# Sheet_1-copy_2025-07-01.net
KiCad netlist of a schematic drawn in Altium Designer
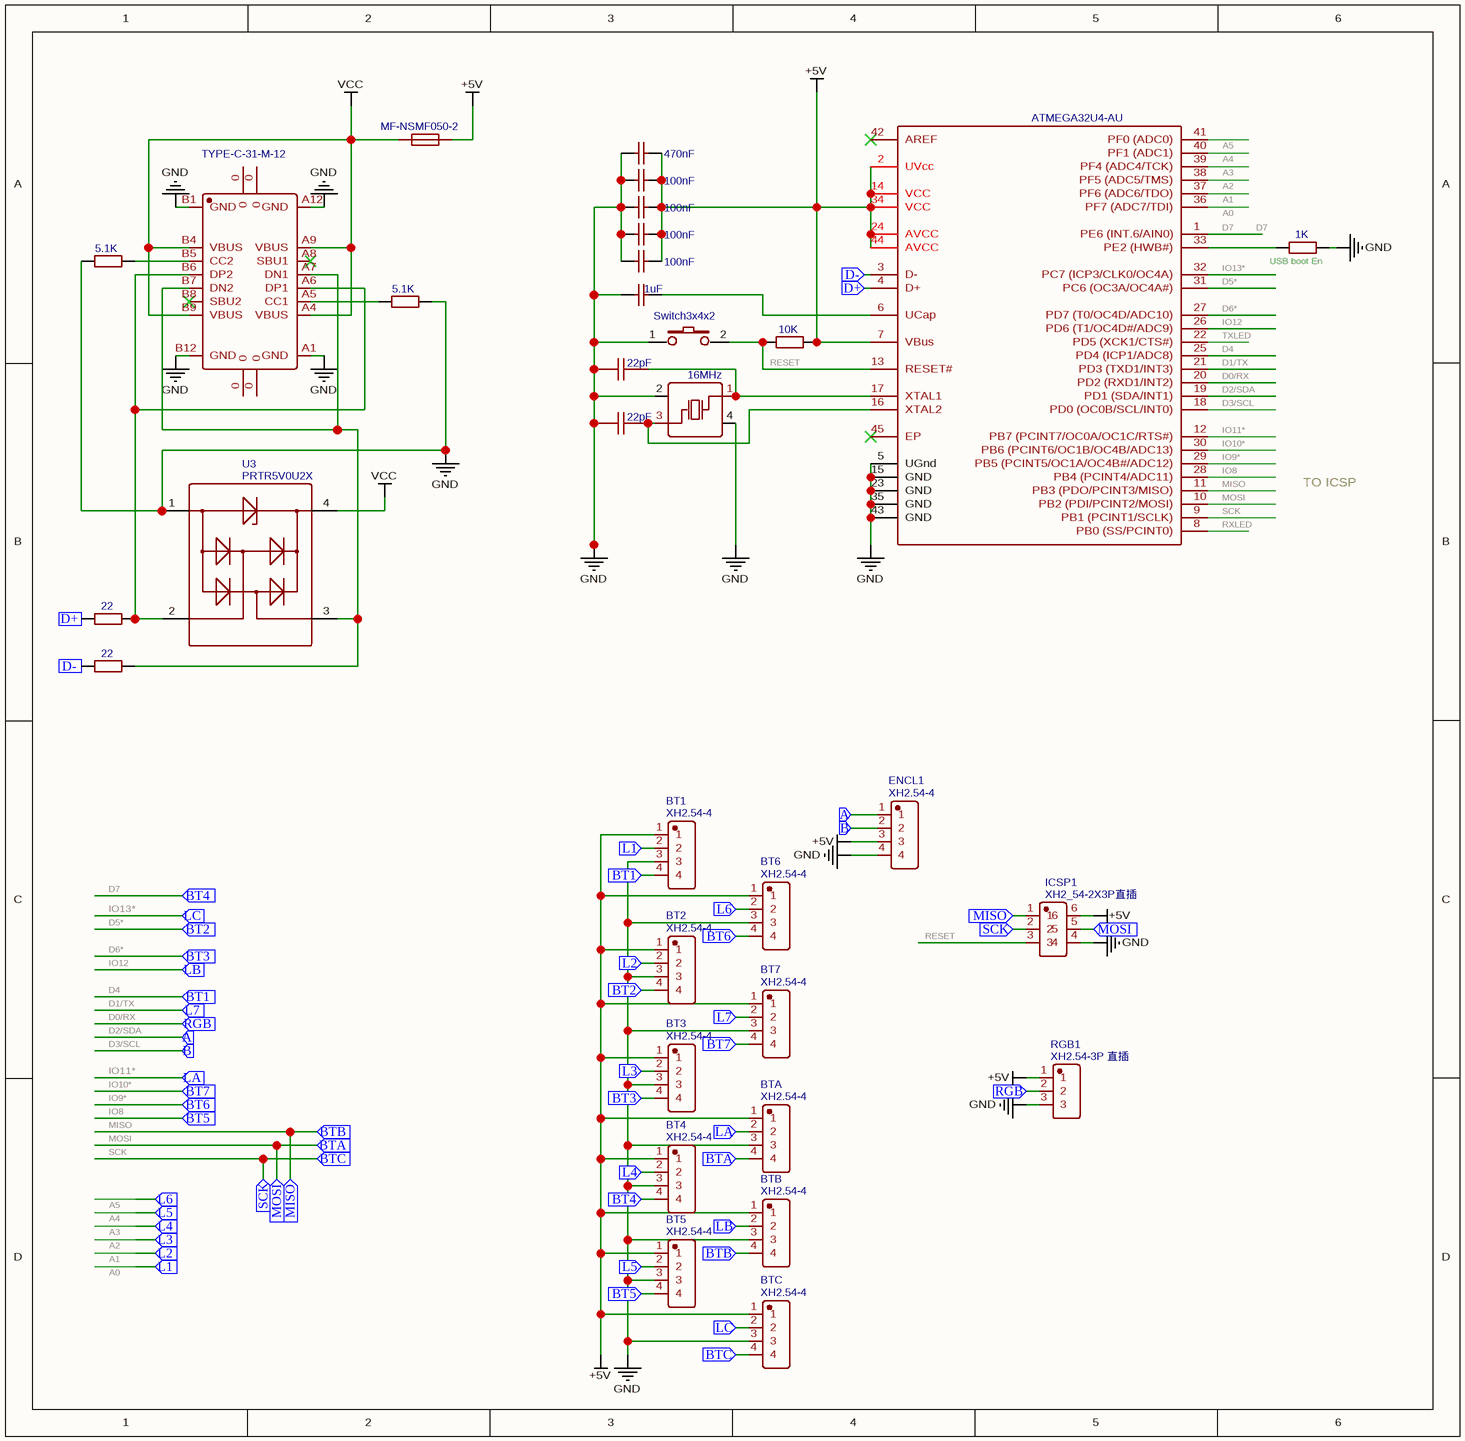
[diagram p0: Sheet_1-copy_2025-07-01.schdoc]

(export (version "E")
  (design (tool "Eeschema 10.0.6"))
  (components
    (comp (ref "BT1")
      (value "XH2.54-4")
      (fields (field (name "CONTRIBUTOR") "LCSC"))
      (libsource (lib "altium-import") (part "root_0_XH2.54-4_"))
    )
    (comp (ref "BT2")
      (value "XH2.54-4")
      (fields (field (name "CONTRIBUTOR") "LCSC"))
      (libsource (lib "altium-import") (part "root_0_XH2.54-4_"))
    )
    (comp (ref "BT3")
      (value "XH2.54-4")
      (fields (field (name "CONTRIBUTOR") "LCSC"))
      (libsource (lib "altium-import") (part "root_0_XH2.54-4_"))
    )
    (comp (ref "BT4")
      (value "XH2.54-4")
      (fields (field (name "CONTRIBUTOR") "LCSC"))
      (libsource (lib "altium-import") (part "root_0_XH2.54-4_"))
    )
    (comp (ref "BT5")
      (value "XH2.54-4")
      (fields (field (name "CONTRIBUTOR") "LCSC"))
      (libsource (lib "altium-import") (part "root_0_XH2.54-4_"))
    )
    (comp (ref "BT6")
      (value "XH2.54-4")
      (fields (field (name "CONTRIBUTOR") "LCSC"))
      (libsource (lib "altium-import") (part "root_0_XH2.54-4_"))
    )
    (comp (ref "BT7")
      (value "XH2.54-4")
      (fields (field (name "CONTRIBUTOR") "LCSC"))
      (libsource (lib "altium-import") (part "root_0_XH2.54-4_"))
    )
    (comp (ref "BTA")
      (value "XH2.54-4")
      (fields (field (name "CONTRIBUTOR") "LCSC"))
      (libsource (lib "altium-import") (part "root_0_XH2.54-4_"))
    )
    (comp (ref "BTB")
      (value "XH2.54-4")
      (fields (field (name "CONTRIBUTOR") "LCSC"))
      (libsource (lib "altium-import") (part "root_0_XH2.54-4_"))
    )
    (comp (ref "BTC")
      (value "XH2.54-4")
      (fields (field (name "CONTRIBUTOR") "LCSC"))
      (libsource (lib "altium-import") (part "root_0_XH2.54-4_"))
    )
    (comp (ref "C9")
      (value "22pF")
      (fields
        (field (name "MANUFACTURER") "SAMSUNG")
        (field (name "MANUFACTURER PART") "CL10C220JB81PNC")
        (field (name "CONTRIBUTOR") "LCSC")
      )
      (libsource (lib "altium-import") (part "root_2_22pF_"))
    )
    (comp (ref "C10")
      (value "22pF")
      (fields
        (field (name "MANUFACTURER") "SAMSUNG")
        (field (name "MANUFACTURER PART") "CL10C220JB81PNC")
        (field (name "CONTRIBUTOR") "LCSC")
      )
      (libsource (lib "altium-import") (part "root_2_22pF_"))
    )
    (comp (ref "C11")
      (value "100nF")
      (fields (field (name "MANUFACTURER PART") "CL10B104JB8NNNC") (field (name "MANUFACTURER") "SAMSUNG"))
      (libsource (lib "altium-import") (part "root_0_100nF_"))
    )
    (comp (ref "C12")
      (value "100nF")
      (fields (field (name "MANUFACTURER PART") "CL10B104JB8NNNC") (field (name "MANUFACTURER") "SAMSUNG"))
      (libsource (lib "altium-import") (part "root_0_100nF_"))
    )
    (comp (ref "C13")
      (value "100nF")
      (fields (field (name "MANUFACTURER PART") "CL10B104JB8NNNC") (field (name "MANUFACTURER") "SAMSUNG"))
      (libsource (lib "altium-import") (part "root_0_100nF_"))
    )
    (comp (ref "C14")
      (value "100nF")
      (fields (field (name "MANUFACTURER PART") "CL10B104JB8NNNC") (field (name "MANUFACTURER") "SAMSUNG"))
      (libsource (lib "altium-import") (part "root_0_100nF_"))
    )
    (comp (ref "C15")
      (value "470nF")
      (fields (field (name "MANUFACTURER PART") "CL10B474KA8NNNC") (field (name "MANUFACTURER") "SAMSUNG"))
      (libsource (lib "altium-import") (part "root_0_470nF_"))
    )
    (comp (ref "C16")
      (value "1uF")
      (fields (field (name "MANUFACTURER PART") "CL10A105KB8NNNC") (field (name "MANUFACTURER") "SAMSUNG"))
      (libsource (lib "altium-import") (part "root_0_1uF_"))
    )
    (comp (ref "ENCL1")
      (value "XH2.54-4")
      (fields (field (name "CONTRIBUTOR") "LCSC"))
      (libsource (lib "altium-import") (part "root_0_XH2.54-4_"))
    )
    (comp (ref "ICSP1")
      (value "XH2_54-2X3P直插")
      (fields (field (name "CONTRIBUTOR") "LCSC"))
      (libsource (lib "altium-import") (part "root_0_XH2_54-2X3P直插_"))
    )
    (comp (ref "KEY2")
      (value "Switch3x4x2")
      (fields (field (name "MANUFACTURER") "ReliaPro"))
      (libsource (lib "altium-import") (part "root_0_Switch3x4x2_"))
    )
    (comp (ref "R1")
      (value "10K")
      (fields (field (name "MANUFACTURER") "UniOhm") (field (name "MANUFACTURER PART") "0805W8F1002T5E"))
      (libsource (lib "altium-import") (part "root_0_10K_"))
    )
    (comp (ref "R2")
      (value "1K")
      (fields (field (name "MANUFACTURER") "UniOhm") (field (name "MANUFACTURER PART") "TC0525F1001T5E"))
      (libsource (lib "altium-import") (part "root_0_1K_"))
    )
    (comp (ref "R3")
      (value "5.1K")
      (fields (field (name "MANUFACTURER") "UniOhm") (field (name "MANUFACTURER PART") "0805W8F5101T5E"))
      (libsource (lib "altium-import") (part "root_0_5.1K_"))
    )
    (comp (ref "R4")
      (value "5.1K")
      (fields (field (name "MANUFACTURER") "UniOhm") (field (name "MANUFACTURER PART") "0805W8F5101T5E"))
      (libsource (lib "altium-import") (part "root_0_5.1K_"))
    )
    (comp (ref "R5")
      (value "22")
      (fields (field (name "MANUFACTURER") "UniOhm") (field (name "MANUFACTURER PART") "0603WAF220JT5E"))
      (libsource (lib "altium-import") (part "root_0_22_"))
    )
    (comp (ref "R6")
      (value "22")
      (fields (field (name "MANUFACTURER") "UniOhm") (field (name "MANUFACTURER PART") "0603WAF220JT5E"))
      (libsource (lib "altium-import") (part "root_0_22_"))
    )
    (comp (ref "RGB1")
      (value "XH2.54-3P 直插")
      (fields (field (name "CONTRIBUTOR") "LCSC"))
      (libsource (lib "altium-import") (part "root_0_XH2.54-3P 直插_"))
    )
    (comp (ref "U2")
      (value "MF-NSMF050-2")
      (fields (field (name "MANUFACTURER") "BOURNS"))
      (libsource (lib "altium-import") (part "root_0_MF-NSMF050-2_"))
    )
    (comp (ref "U3")
      (value "PRTR5V0U2X")
      (fields (field (name "MANUFACTURER") "Yenji Elec") (field (name "CONTRIBUTOR") "LCSC"))
      (libsource (lib "altium-import") (part "root_0_PRTR5V0U2X_"))
    )
    (comp (ref "U77")
      (value "ATMEGA32U4-AU")
      (fields (field (name "MANUFACTURER") "MICROCHIP") (field (name "MANUFACTURER PART") "ATMEGA32U4-MU"))
      (libsource (lib "altium-import") (part "root_0_ATMEGA32U4-AU_"))
    )
    (comp (ref "USBC2")
      (value "TYPE-C-31-M-12")
      (fields
        (field (name "MANUFACTURER") "Rectangular Connectors - Contacts")
        (field (name "CONTRIBUTOR") "LCSC")
      )
      (libsource (lib "altium-import") (part "root_0_TYPE-C-31-M-12_"))
    )
    (comp (ref "X1")
      (value "16MHz")
      (fields (field (name "MANUFACTURER") "YXC") (field (name "MANUFACTURER PART") "X322516MRB4SI"))
      (libsource (lib "altium-import") (part "root_2_16MHz_"))
    )
  )
  (nets
    (net (code "1") (name "+5V") (class "Default")
      (node (ref "BT1") (pin "1") (pinfunction "1_1") (pintype "passive"))
      (node (ref "BT2") (pin "1") (pinfunction "1_1") (pintype "passive"))
      (node (ref "BT3") (pin "1") (pinfunction "1_1") (pintype "passive"))
      (node (ref "BT4") (pin "1") (pinfunction "1_1") (pintype "passive"))
      (node (ref "BT5") (pin "1") (pinfunction "1_1") (pintype "passive"))
      (node (ref "BT6") (pin "1") (pinfunction "1_1") (pintype "passive"))
      (node (ref "BT7") (pin "1") (pinfunction "1_1") (pintype "passive"))
      (node (ref "BTA") (pin "1") (pinfunction "1_1") (pintype "passive"))
      (node (ref "BTB") (pin "1") (pinfunction "1_1") (pintype "passive"))
      (node (ref "BTC") (pin "1") (pinfunction "1_1") (pintype "passive"))
      (node (ref "C11") (pin "2") (pinfunction "2_2") (pintype "passive"))
      (node (ref "C12") (pin "2") (pinfunction "2_2") (pintype "passive"))
      (node (ref "C13") (pin "2") (pinfunction "2_2") (pintype "passive"))
      (node (ref "C14") (pin "2") (pinfunction "2_2") (pintype "passive"))
      (node (ref "C15") (pin "2") (pinfunction "2_2") (pintype "passive"))
      (node (ref "ENCL1") (pin "3") (pinfunction "3_3") (pintype "passive"))
      (node (ref "ICSP1") (pin "6") (pinfunction "6_6") (pintype "passive"))
      (node (ref "R1") (pin "2") (pinfunction "2_2") (pintype "passive"))
      (node (ref "RGB1") (pin "1") (pinfunction "1_1") (pintype "passive"))
      (node (ref "U2") (pin "2") (pinfunction "2_2") (pintype "passive"))
      (node (ref "U77") (pin "14") (pinfunction "VCC_14") (pintype "passive"))
      (node (ref "U77") (pin "2") (pinfunction "UVcc_2") (pintype "passive"))
      (node (ref "U77") (pin "24") (pinfunction "AVCC_24") (pintype "passive"))
      (node (ref "U77") (pin "34") (pinfunction "VCC_34") (pintype "passive"))
      (node (ref "U77") (pin "44") (pinfunction "AVCC_44") (pintype "passive"))
      (node (ref "U77") (pin "7") (pinfunction "VBus_7") (pintype "passive"))
    )
    (net (code "2") (name "/A0") (class "Default")
      (node (ref "BT1") (pin "2") (pinfunction "2_2") (pintype "passive"))
      (node (ref "U77") (pin "36") (pinfunction "PF7_(ADC7/TDI)_36") (pintype "passive"))
    )
    (net (code "3") (name "/A1") (class "Default")
      (node (ref "BT2") (pin "2") (pinfunction "2_2") (pintype "passive"))
      (node (ref "U77") (pin "37") (pinfunction "PF6_(ADC6/TDO)_37") (pintype "passive"))
    )
    (net (code "4") (name "/A2") (class "Default")
      (node (ref "BT3") (pin "2") (pinfunction "2_2") (pintype "passive"))
      (node (ref "U77") (pin "38") (pinfunction "PF5_(ADC5/TMS)_38") (pintype "passive"))
    )
    (net (code "5") (name "/A3") (class "Default")
      (node (ref "BT4") (pin "2") (pinfunction "2_2") (pintype "passive"))
      (node (ref "U77") (pin "39") (pinfunction "PF4_(ADC4/TCK)_39") (pintype "passive"))
    )
    (net (code "6") (name "/A4") (class "Default")
      (node (ref "BT5") (pin "2") (pinfunction "2_2") (pintype "passive"))
      (node (ref "U77") (pin "40") (pinfunction "PF1_(ADC1)_40") (pintype "passive"))
    )
    (net (code "7") (name "/A5") (class "Default")
      (node (ref "BT6") (pin "2") (pinfunction "2_2") (pintype "passive"))
      (node (ref "U77") (pin "41") (pinfunction "PF0_(ADC0)_41") (pintype "passive"))
    )
    (net (code "8") (name "/D+") (class "Default")
      (node (ref "R5") (pin "1") (pinfunction "1_1") (pintype "passive"))
      (node (ref "U77") (pin "4") (pinfunction "D+_4") (pintype "passive"))
    )
    (net (code "9") (name "/D-") (class "Default")
      (node (ref "R6") (pin "1") (pinfunction "1_1") (pintype "passive"))
      (node (ref "U77") (pin "3") (pinfunction "D-_3") (pintype "passive"))
    )
    (net (code "10") (name "/D0{slash}RX") (class "Default")
      (node (ref "RGB1") (pin "2") (pinfunction "2_2") (pintype "passive"))
      (node (ref "U77") (pin "20") (pinfunction "PD2_(RXD1/INT2)_20") (pintype "passive"))
    )
    (net (code "11") (name "/D1{slash}TX") (class "Default")
      (node (ref "BT7") (pin "2") (pinfunction "2_2") (pintype "passive"))
      (node (ref "U77") (pin "21") (pinfunction "PD3_(TXD1/INT3)_21") (pintype "passive"))
    )
    (net (code "12") (name "/D2{slash}SDA") (class "Default")
      (node (ref "ENCL1") (pin "1") (pinfunction "1_1") (pintype "passive"))
      (node (ref "U77") (pin "19") (pinfunction "PD1_(SDA/INT1)_19") (pintype "passive"))
    )
    (net (code "13") (name "/D3{slash}SCL") (class "Default")
      (node (ref "ENCL1") (pin "2") (pinfunction "2_2") (pintype "passive"))
      (node (ref "U77") (pin "18") (pinfunction "PD0_(OC0B/SCL/INT0)_18") (pintype "passive"))
    )
    (net (code "14") (name "/D4") (class "Default")
      (node (ref "BT1") (pin "4") (pinfunction "4_4") (pintype "passive"))
      (node (ref "U77") (pin "25") (pinfunction "PD4_(ICP1/ADC8)_25") (pintype "passive"))
    )
    (net (code "15") (name "/D5*") (class "Default")
      (node (ref "BT2") (pin "4") (pinfunction "4_4") (pintype "passive"))
      (node (ref "U77") (pin "31") (pinfunction "PC6_(OC3A/OC4A#)_31") (pintype "passive"))
    )
    (net (code "16") (name "/D6*") (class "Default")
      (node (ref "BT3") (pin "4") (pinfunction "4_4") (pintype "passive"))
      (node (ref "U77") (pin "27") (pinfunction "PD7_(T0/OC4D/ADC10)_27") (pintype "passive"))
    )
    (net (code "17") (name "/D7") (class "Default")
      (node (ref "BT4") (pin "4") (pinfunction "4_4") (pintype "passive"))
      (node (ref "U77") (pin "1") (pinfunction "PE6_(INT.6/AIN0)_1") (pintype "passive"))
    )
    (net (code "18") (name "/IO8") (class "Default")
      (node (ref "BT5") (pin "4") (pinfunction "4_4") (pintype "passive"))
      (node (ref "U77") (pin "28") (pinfunction "PB4_(PCINT4/ADC11)_28") (pintype "passive"))
    )
    (net (code "19") (name "/IO9*") (class "Default")
      (node (ref "BT6") (pin "4") (pinfunction "4_4") (pintype "passive"))
      (node (ref "U77") (pin "29") (pinfunction "PB5_(PCINT5/OC1A/OC4B#/ADC12)_29") (pintype "passive"))
    )
    (net (code "20") (name "/IO10*") (class "Default")
      (node (ref "BT7") (pin "4") (pinfunction "4_4") (pintype "passive"))
      (node (ref "U77") (pin "30") (pinfunction "PB6_(PCINT6/OC1B/OC4B/ADC13)_30") (pintype "passive"))
    )
    (net (code "21") (name "/IO11*") (class "Default")
      (node (ref "BTA") (pin "2") (pinfunction "2_2") (pintype "passive"))
      (node (ref "U77") (pin "12") (pinfunction "PB7_(PCINT7/OC0A/OC1C/RTS#)_12") (pintype "passive"))
    )
    (net (code "22") (name "/IO12") (class "Default")
      (node (ref "BTB") (pin "2") (pinfunction "2_2") (pintype "passive"))
      (node (ref "U77") (pin "26") (pinfunction "PD6_(T1/OC4D#/ADC9)_26") (pintype "passive"))
    )
    (net (code "23") (name "/IO13*") (class "Default")
      (node (ref "BTC") (pin "2") (pinfunction "2_2") (pintype "passive"))
      (node (ref "U77") (pin "32") (pinfunction "PC7_(ICP3/CLK0/OC4A)_32") (pintype "passive"))
    )
    (net (code "24") (name "/MISO") (class "Default")
      (node (ref "BTB") (pin "4") (pinfunction "4_4") (pintype "passive"))
      (node (ref "ICSP1") (pin "1") (pinfunction "1_1") (pintype "passive"))
      (node (ref "U77") (pin "11") (pinfunction "PB3_(PDO/PCINT3/MISO)_11") (pintype "passive"))
    )
    (net (code "25") (name "/MOSI") (class "Default")
      (node (ref "BTA") (pin "4") (pinfunction "4_4") (pintype "passive"))
      (node (ref "ICSP1") (pin "5") (pinfunction "5_5") (pintype "passive"))
      (node (ref "U77") (pin "10") (pinfunction "PB2_(PDI/PCINT2/MOSI)_10") (pintype "passive"))
    )
    (net (code "26") (name "/RESET") (class "Default")
      (node (ref "ICSP1") (pin "3") (pinfunction "3_3") (pintype "passive"))
      (node (ref "KEY2") (pin "2") (pinfunction "2_2") (pintype "passive"))
      (node (ref "R1") (pin "1") (pinfunction "1_1") (pintype "passive"))
      (node (ref "U77") (pin "13") (pinfunction "RESET#_13") (pintype "passive"))
    )
    (net (code "27") (name "/RXLED") (class "Default")
      (node (ref "U77") (pin "8") (pinfunction "PB0_(SS/PCINT0)_8") (pintype "passive"))
    )
    (net (code "28") (name "/SCK") (class "Default")
      (node (ref "BTC") (pin "4") (pinfunction "4_4") (pintype "passive"))
      (node (ref "ICSP1") (pin "2") (pinfunction "2_2") (pintype "passive"))
      (node (ref "U77") (pin "9") (pinfunction "PB1_(PCINT1/SCLK)_9") (pintype "passive"))
    )
    (net (code "29") (name "/TXLED") (class "Default")
      (node (ref "U77") (pin "22") (pinfunction "PD5_(XCK1/CTS#)_22") (pintype "passive"))
    )
    (net (code "30") (name "GND") (class "Default")
      (node (ref "BT1") (pin "3") (pinfunction "3_3") (pintype "passive"))
      (node (ref "BT2") (pin "3") (pinfunction "3_3") (pintype "passive"))
      (node (ref "BT3") (pin "3") (pinfunction "3_3") (pintype "passive"))
      (node (ref "BT4") (pin "3") (pinfunction "3_3") (pintype "passive"))
      (node (ref "BT5") (pin "3") (pinfunction "3_3") (pintype "passive"))
      (node (ref "BT6") (pin "3") (pinfunction "3_3") (pintype "passive"))
      (node (ref "BT7") (pin "3") (pinfunction "3_3") (pintype "passive"))
      (node (ref "BTA") (pin "3") (pinfunction "3_3") (pintype "passive"))
      (node (ref "BTB") (pin "3") (pinfunction "3_3") (pintype "passive"))
      (node (ref "BTC") (pin "3") (pinfunction "3_3") (pintype "passive"))
      (node (ref "C10") (pin "1") (pinfunction "1_1") (pintype "passive"))
      (node (ref "C11") (pin "1") (pinfunction "1_1") (pintype "passive"))
      (node (ref "C12") (pin "1") (pinfunction "1_1") (pintype "passive"))
      (node (ref "C13") (pin "1") (pinfunction "1_1") (pintype "passive"))
      (node (ref "C14") (pin "1") (pinfunction "1_1") (pintype "passive"))
      (node (ref "C15") (pin "1") (pinfunction "1_1") (pintype "passive"))
      (node (ref "C16") (pin "1") (pinfunction "1_1") (pintype "passive"))
      (node (ref "C9") (pin "1") (pinfunction "1_1") (pintype "passive"))
      (node (ref "ENCL1") (pin "4") (pinfunction "4_4") (pintype "passive"))
      (node (ref "ICSP1") (pin "4") (pinfunction "4_4") (pintype "passive"))
      (node (ref "KEY2") (pin "1") (pinfunction "1_1") (pintype "passive"))
      (node (ref "R2") (pin "2") (pinfunction "2_2") (pintype "passive"))
      (node (ref "R3") (pin "2") (pinfunction "2_2") (pintype "passive"))
      (node (ref "R4") (pin "1") (pinfunction "1_1") (pintype "passive"))
      (node (ref "RGB1") (pin "3") (pinfunction "3_3") (pintype "passive"))
      (node (ref "U3") (pin "1") (pinfunction "GND_1") (pintype "passive"))
      (node (ref "U77") (pin "15") (pinfunction "GND_15") (pintype "passive"))
      (node (ref "U77") (pin "23") (pinfunction "GND_23") (pintype "passive"))
      (node (ref "U77") (pin "35") (pinfunction "GND_35") (pintype "passive"))
      (node (ref "U77") (pin "43") (pinfunction "GND_43") (pintype "passive"))
      (node (ref "U77") (pin "5") (pinfunction "UGnd_5") (pintype "passive"))
      (node (ref "USBC2") (pin "A1") (pinfunction "GND_A1") (pintype "passive"))
      (node (ref "USBC2") (pin "A12") (pinfunction "GND_A12") (pintype "passive"))
      (node (ref "USBC2") (pin "B1") (pinfunction "GND_B1") (pintype "passive"))
      (node (ref "USBC2") (pin "B12") (pinfunction "GND_B12") (pintype "passive"))
      (node (ref "X1") (pin "2") (pinfunction "GND_2") (pintype "passive"))
      (node (ref "X1") (pin "4") (pinfunction "GND_4") (pintype "passive"))
    )
    (net (code "31") (name "Net-(U3-IO1)") (class "Default")
      (node (ref "R5") (pin "2") (pinfunction "2_2") (pintype "passive"))
      (node (ref "U3") (pin "2") (pinfunction "IO1_2") (pintype "passive"))
      (node (ref "USBC2") (pin "A6") (pinfunction "DP1_A6") (pintype "passive"))
      (node (ref "USBC2") (pin "B6") (pinfunction "DP2_B6") (pintype "passive"))
    )
    (net (code "32") (name "Net-(U3-IO2)") (class "Default")
      (node (ref "R6") (pin "2") (pinfunction "2_2") (pintype "passive"))
      (node (ref "U3") (pin "3") (pinfunction "IO2_3") (pintype "passive"))
      (node (ref "USBC2") (pin "A7") (pinfunction "DN1_A7") (pintype "passive"))
      (node (ref "USBC2") (pin "B7") (pinfunction "DN2_B7") (pintype "passive"))
    )
    (net (code "33") (name "Net-(U77-PE2_(HWB#))") (class "Default")
      (node (ref "R2") (pin "1") (pinfunction "1_1") (pintype "passive"))
      (node (ref "U77") (pin "33") (pinfunction "PE2_(HWB#)_33") (pintype "passive"))
    )
    (net (code "34") (name "Net-(U77-UCap)") (class "Default")
      (node (ref "C16") (pin "2") (pinfunction "2_2") (pintype "passive"))
      (node (ref "U77") (pin "6") (pinfunction "UCap_6") (pintype "passive"))
    )
    (net (code "35") (name "Net-(U77-XTAL1)") (class "Default")
      (node (ref "C9") (pin "2") (pinfunction "2_2") (pintype "passive"))
      (node (ref "U77") (pin "17") (pinfunction "XTAL1_17") (pintype "passive"))
      (node (ref "X1") (pin "1") (pinfunction "OSC1_1") (pintype "passive"))
    )
    (net (code "36") (name "Net-(U77-XTAL2)") (class "Default")
      (node (ref "C10") (pin "2") (pinfunction "2_2") (pintype "passive"))
      (node (ref "U77") (pin "16") (pinfunction "XTAL2_16") (pintype "passive"))
      (node (ref "X1") (pin "3") (pinfunction "OSC2_3") (pintype "passive"))
    )
    (net (code "37") (name "Net-(USBC2-CC1)") (class "Default")
      (node (ref "R3") (pin "1") (pinfunction "1_1") (pintype "passive"))
      (node (ref "USBC2") (pin "A5") (pinfunction "CC1_A5") (pintype "passive"))
    )
    (net (code "38") (name "Net-(USBC2-CC2)") (class "Default")
      (node (ref "R4") (pin "2") (pinfunction "2_2") (pintype "passive"))
      (node (ref "USBC2") (pin "B5") (pinfunction "CC2_B5") (pintype "passive"))
    )
    (net (code "39") (name "VCC") (class "Default")
      (node (ref "U2") (pin "1") (pinfunction "1_1") (pintype "passive"))
      (node (ref "U3") (pin "4") (pinfunction "VCC_4") (pintype "passive"))
      (node (ref "USBC2") (pin "A4") (pinfunction "VBUS_A4") (pintype "passive"))
      (node (ref "USBC2") (pin "A9") (pinfunction "VBUS_A9") (pintype "passive"))
      (node (ref "USBC2") (pin "B4") (pinfunction "VBUS_B4") (pintype "passive"))
      (node (ref "USBC2") (pin "B9") (pinfunction "VBUS_B9") (pintype "passive"))
    )
    (net (code "40") (name "unconnected-(U77-AREF-Pad42)") (class "Default")
      (node (ref "U77") (pin "42") (pinfunction "AREF_42") (pintype "passive+no_connect"))
    )
    (net (code "41") (name "unconnected-(U77-EP-Pad45)") (class "Default")
      (node (ref "U77") (pin "45") (pinfunction "EP_45") (pintype "passive+no_connect"))
    )
    (net (code "42") (name "unconnected-(USBC2-Pad0)") (class "Default")
      (node (ref "USBC2") (pin "0") (pinfunction "0_0") (pintype "passive"))
    )
    (net (code "43") (name "unconnected-(USBC2-Pad0)_1") (class "Default")
      (node (ref "USBC2") (pin "0") (pinfunction "0_0") (pintype "passive"))
    )
    (net (code "44") (name "unconnected-(USBC2-Pad0)_2") (class "Default")
      (node (ref "USBC2") (pin "0") (pinfunction "0_0") (pintype "passive"))
    )
    (net (code "45") (name "unconnected-(USBC2-Pad0)_3") (class "Default")
      (node (ref "USBC2") (pin "0") (pinfunction "0_0") (pintype "passive"))
    )
    (net (code "46") (name "unconnected-(USBC2-SBU1-PadA8)") (class "Default")
      (node (ref "USBC2") (pin "A8") (pinfunction "SBU1_A8") (pintype "passive+no_connect"))
    )
    (net (code "47") (name "unconnected-(USBC2-SBU2-PadB8)") (class "Default")
      (node (ref "USBC2") (pin "B8") (pinfunction "SBU2_B8") (pintype "passive+no_connect"))
    )
  )
)
